# Converter_Schematic.net
KiCad netlist of a schematic drawn in Altium Designer
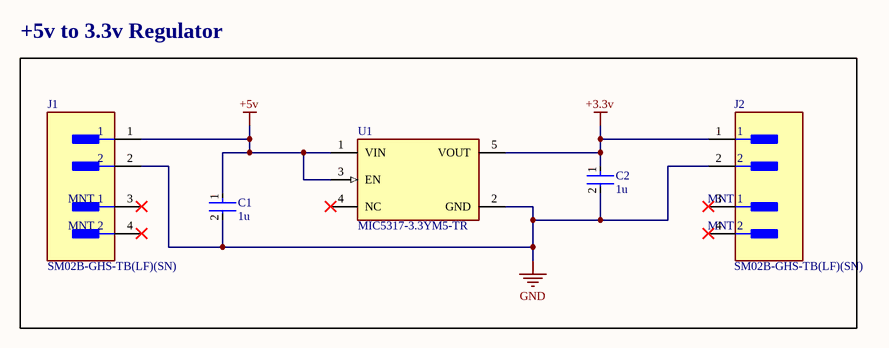
[diagram p0: Converter_Schematic.SchDoc]

(export (version "E")
  (design (tool "Eeschema 10.0.6"))
  (components
    (comp (ref "C1")
      (value "1u")
      (footprint "FP-CC0805-0_85-MFG")
      (description "CAP CER 1UF 10V X5R 0805")
      (fields
        (field (name "TOLERANCE") "0.1")
        (field (name "OCTOPART") "https://octopart.com/cc0805kkx5r6bb105-yageo-9292777")
      )
      (libsource (lib "Altium Content Vault") (part "11868f565c42a9108669ba33697ecf6"))
    )
    (comp (ref "C2")
      (value "1u")
      (footprint "FP-CC0805-0_85-MFG")
      (description "CAP CER 1UF 10V X5R 0805")
      (fields
        (field (name "TOLERANCE") "0.1")
        (field (name "OCTOPART") "https://octopart.com/cc0805kkx5r6bb105-yageo-9292777")
      )
      (libsource (lib "Altium Content Vault") (part "11868f565c42a9108669ba33697ecf6"))
    )
    (comp (ref "J1")
      (value "SM02B-GHS-TB(LF)(SN)")
      (footprint "FP-SM02B-GHS-TB_LF_SN-MFG")
      (description "CONN HEADER SMD R/A 2POS 1.25MM")
      (libsource (lib "Altium Content Vault") (part "56ec3178a87b3978bdc1b3682cd516a"))
    )
    (comp (ref "J2")
      (value "SM02B-GHS-TB(LF)(SN)")
      (footprint "FP-SM02B-GHS-TB_LF_SN-MFG")
      (description "CONN HEADER SMD R/A 2POS 1.25MM")
      (libsource (lib "") (part "56ec3178a87b3978bdc1b3682cd516a_1"))
    )
    (comp (ref "U1")
      (value "MIC5317-3.3YM5-TR")
      (footprint "FP-SOT23-5LD-PL-1-MFG")
      (description "IC REG LINEAR 3.3V 150MA SOT23-5")
      (libsource (lib "Altium Content Vault") (part "0a093dae7315cdc977fd108dde87457"))
    )
  )
  (nets
    (net (code "1") (name "+3.3v") (class "Default")
      (node (ref "C2") (pin "1") (pinfunction "1_1") (pintype "passive"))
      (node (ref "J2") (pin "1") (pinfunction "1_1") (pintype "passive"))
      (node (ref "U1") (pin "5") (pinfunction "VOUT_5") (pintype "power_in"))
    )
    (net (code "2") (name "+5v") (class "Default")
      (node (ref "C1") (pin "1") (pinfunction "1_1") (pintype "passive"))
      (node (ref "J1") (pin "1") (pinfunction "1_1") (pintype "passive"))
      (node (ref "U1") (pin "1") (pinfunction "VIN_1") (pintype "power_in"))
      (node (ref "U1") (pin "3") (pinfunction "EN_3") (pintype "input"))
    )
    (net (code "3") (name "GND") (class "Default")
      (node (ref "C1") (pin "2") (pinfunction "2_2") (pintype "passive"))
      (node (ref "C2") (pin "2") (pinfunction "2_2") (pintype "passive"))
      (node (ref "J1") (pin "2") (pinfunction "2_2") (pintype "passive"))
      (node (ref "J2") (pin "2") (pinfunction "2_2") (pintype "passive"))
      (node (ref "U1") (pin "2") (pinfunction "GND_2") (pintype "power_in"))
    )
    (net (code "4") (name "unconnected-(J1-MNT_1-Pad3)") (class "Default")
      (node (ref "J1") (pin "3") (pinfunction "MNT_1_3") (pintype "passive+no_connect"))
    )
    (net (code "5") (name "unconnected-(J1-MNT_2-Pad4)") (class "Default")
      (node (ref "J1") (pin "4") (pinfunction "MNT_2_4") (pintype "passive+no_connect"))
    )
    (net (code "6") (name "unconnected-(J2-MNT_1-Pad3)") (class "Default")
      (node (ref "J2") (pin "3") (pinfunction "MNT_1_3") (pintype "passive+no_connect"))
    )
    (net (code "7") (name "unconnected-(J2-MNT_2-Pad4)") (class "Default")
      (node (ref "J2") (pin "4") (pinfunction "MNT_2_4") (pintype "passive+no_connect"))
    )
    (net (code "8") (name "unconnected-(U1-NC-Pad4)") (class "Default")
      (node (ref "U1") (pin "4") (pinfunction "NC_4") (pintype "passive+no_connect"))
    )
  )
)
